# WL-Power.net
KiCad netlist of a schematic drawn in Altium Designer
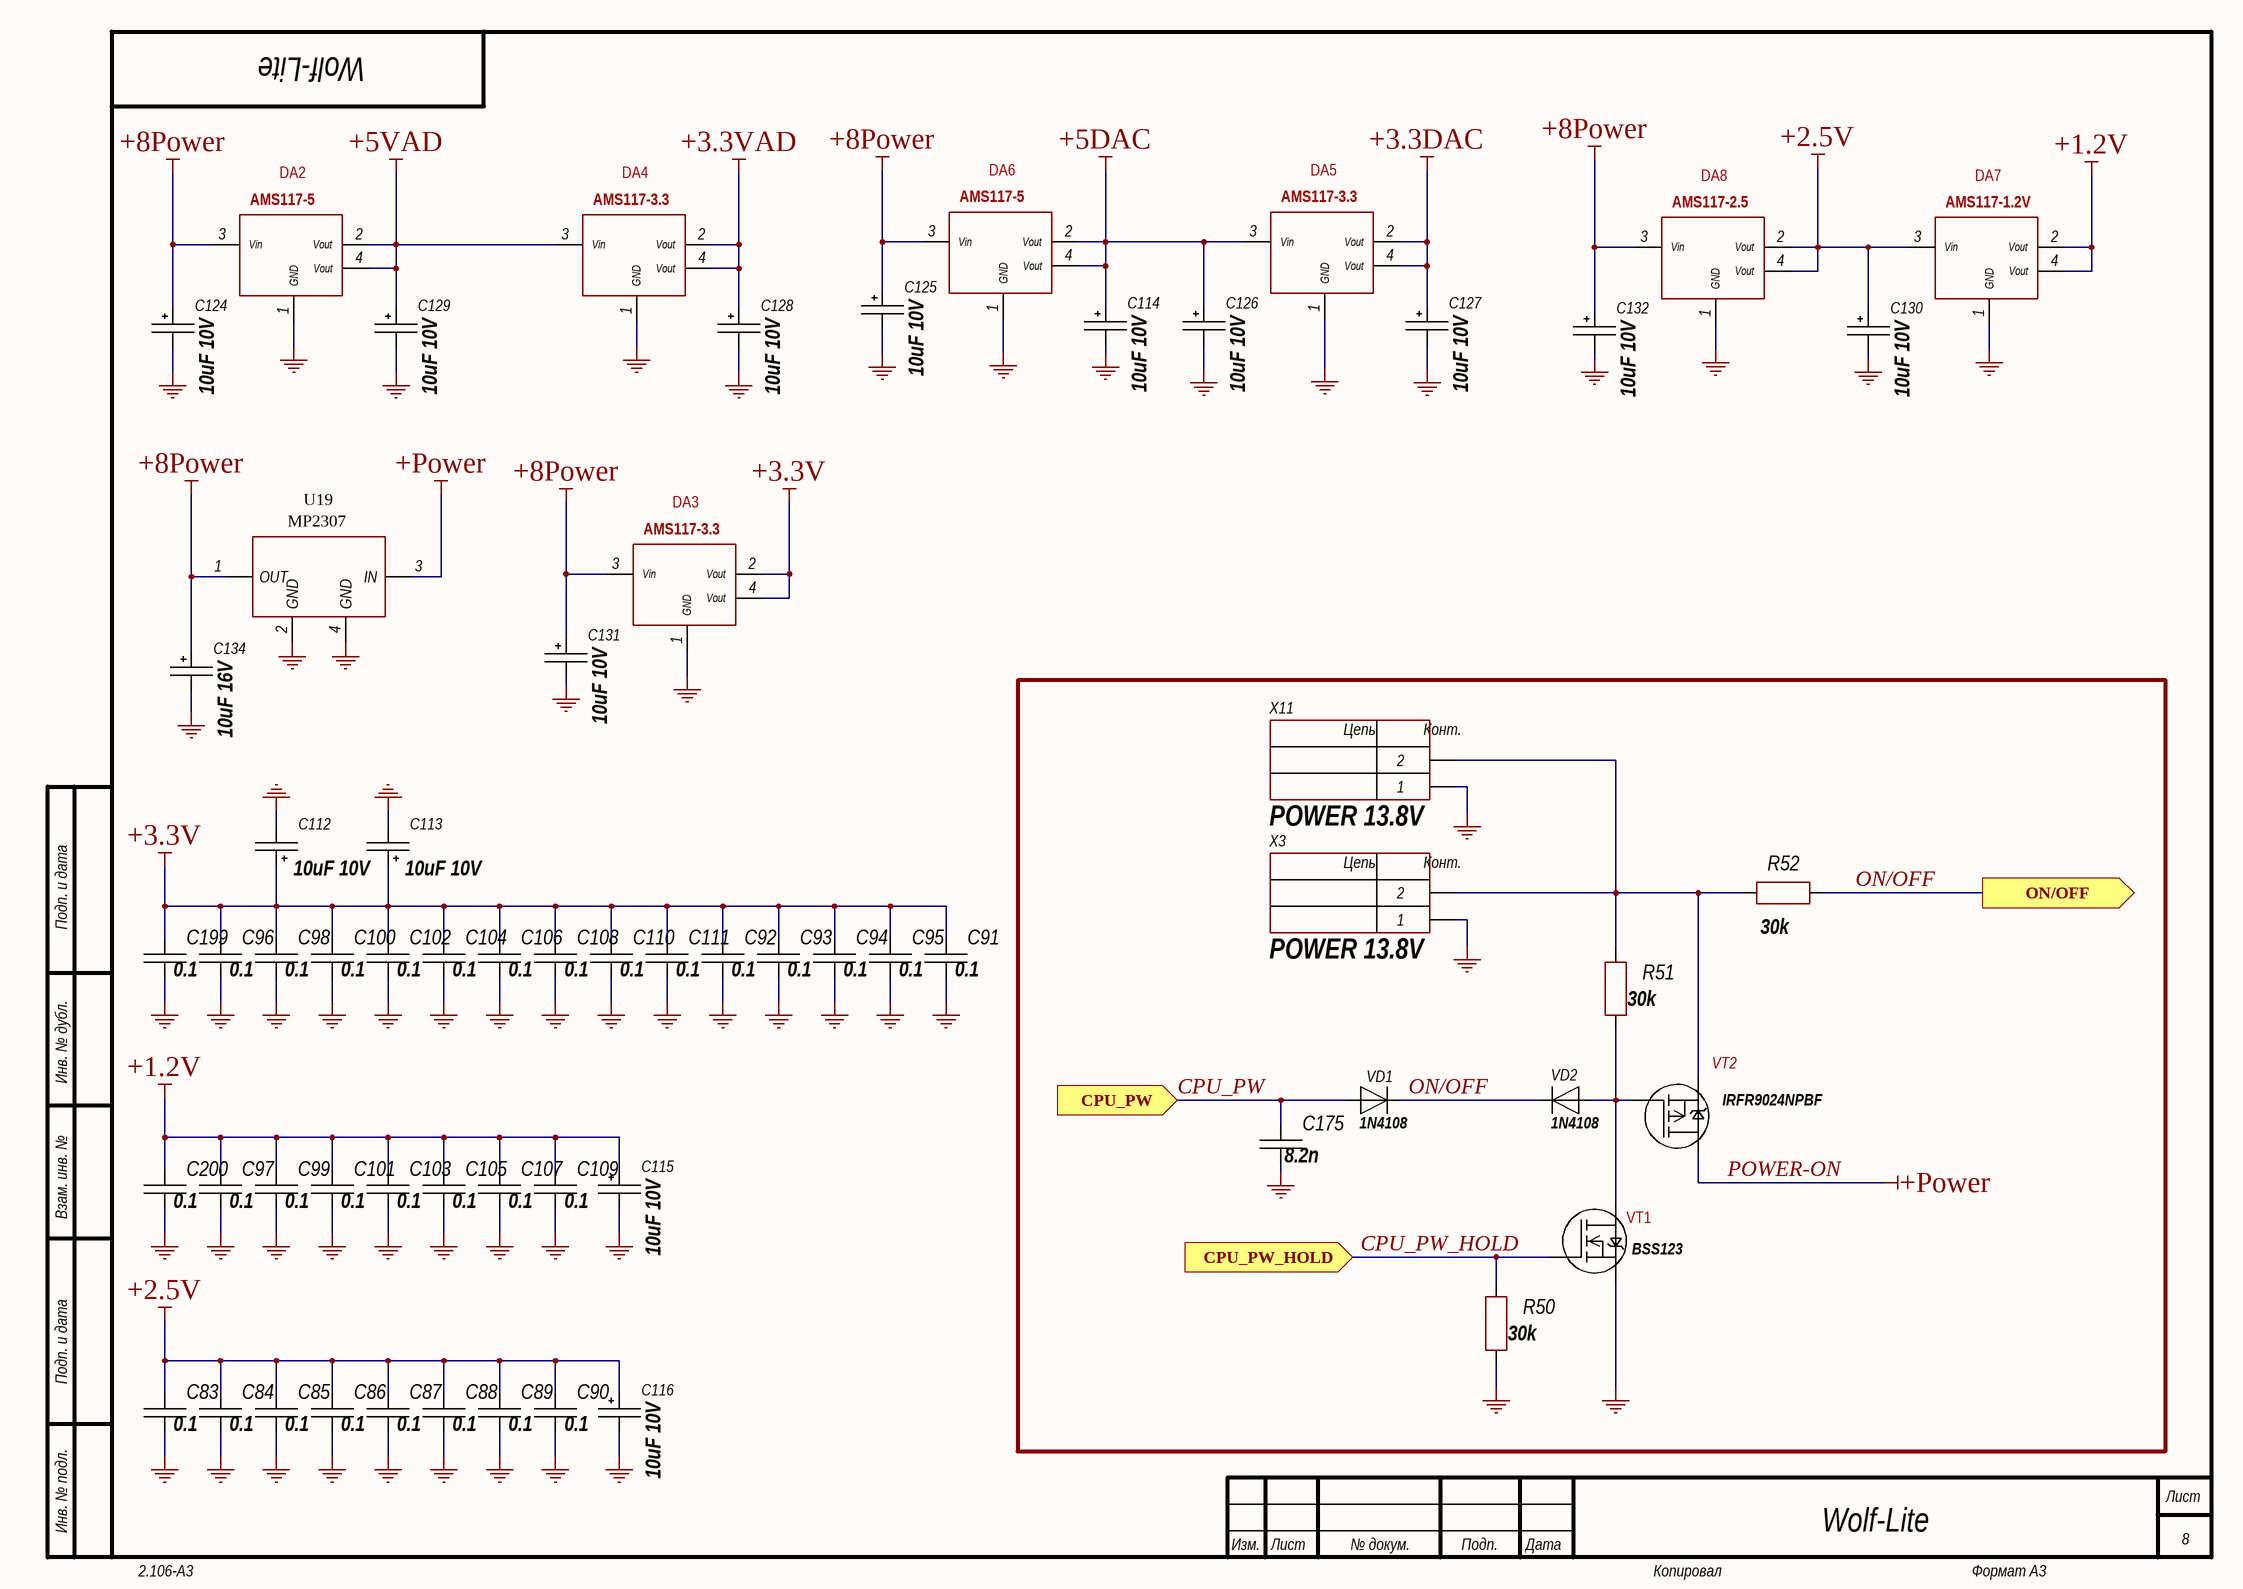
[diagram p0: WL-Power.SchDoc]

(export (version "E")
  (design (tool "Eeschema 10.0.6"))
  (components
    (comp (ref "C83")
      (value "0.1")
      (footprint "standard:CH0805C")
      (libsource (lib "Discrete") (part "Capacitor"))
    )
    (comp (ref "C84")
      (value "0.1")
      (footprint "standard:CH0805C")
      (libsource (lib "Discrete") (part "Capacitor"))
    )
    (comp (ref "C85")
      (value "0.1")
      (footprint "standard:CH0805C")
      (libsource (lib "Discrete") (part "Capacitor"))
    )
    (comp (ref "C86")
      (value "0.1")
      (footprint "standard:CH0805C")
      (libsource (lib "Discrete") (part "Capacitor"))
    )
    (comp (ref "C87")
      (value "0.1")
      (footprint "standard:CH0805C")
      (libsource (lib "Discrete") (part "Capacitor"))
    )
    (comp (ref "C88")
      (value "0.1")
      (footprint "standard:CH0805C")
      (libsource (lib "Discrete") (part "Capacitor"))
    )
    (comp (ref "C89")
      (value "0.1")
      (footprint "standard:CH0805C")
      (libsource (lib "Discrete") (part "Capacitor"))
    )
    (comp (ref "C90")
      (value "0.1")
      (footprint "standard:CH0805C")
      (libsource (lib "Discrete") (part "Capacitor"))
    )
    (comp (ref "C91")
      (value "0.1")
      (footprint "standard:CH0805C")
      (libsource (lib "Discrete") (part "Capacitor"))
    )
    (comp (ref "C92")
      (value "0.1")
      (footprint "standard:CH0805C")
      (libsource (lib "Discrete") (part "Capacitor"))
    )
    (comp (ref "C93")
      (value "0.1")
      (footprint "standard:CH0805C")
      (libsource (lib "Discrete") (part "Capacitor"))
    )
    (comp (ref "C94")
      (value "0.1")
      (footprint "standard:CH0805C")
      (libsource (lib "Discrete") (part "Capacitor"))
    )
    (comp (ref "C95")
      (value "0.1")
      (footprint "standard:CH0805C")
      (libsource (lib "Discrete") (part "Capacitor"))
    )
    (comp (ref "C96")
      (value "0.1")
      (footprint "standard:CH0805C")
      (libsource (lib "Discrete") (part "Capacitor"))
    )
    (comp (ref "C97")
      (value "0.1")
      (footprint "standard:CH0805C")
      (libsource (lib "Discrete") (part "Capacitor"))
    )
    (comp (ref "C98")
      (value "0.1")
      (footprint "standard:CH0805C")
      (libsource (lib "Discrete") (part "Capacitor"))
    )
    (comp (ref "C99")
      (value "0.1")
      (footprint "standard:CH0805C")
      (libsource (lib "Discrete") (part "Capacitor"))
    )
    (comp (ref "C100")
      (value "0.1")
      (footprint "standard:CH0805C")
      (libsource (lib "Discrete") (part "Capacitor"))
    )
    (comp (ref "C101")
      (value "0.1")
      (footprint "standard:CH0805C")
      (libsource (lib "Discrete") (part "Capacitor"))
    )
    (comp (ref "C102")
      (value "0.1")
      (footprint "standard:CH0805C")
      (libsource (lib "Discrete") (part "Capacitor"))
    )
    (comp (ref "C103")
      (value "0.1")
      (footprint "standard:CH0805C")
      (libsource (lib "Discrete") (part "Capacitor"))
    )
    (comp (ref "C104")
      (value "0.1")
      (footprint "standard:CH0805C")
      (libsource (lib "Discrete") (part "Capacitor"))
    )
    (comp (ref "C105")
      (value "0.1")
      (footprint "standard:CH0805C")
      (libsource (lib "Discrete") (part "Capacitor"))
    )
    (comp (ref "C106")
      (value "0.1")
      (footprint "standard:CH0805C")
      (libsource (lib "Discrete") (part "Capacitor"))
    )
    (comp (ref "C107")
      (value "0.1")
      (footprint "standard:CH0805C")
      (libsource (lib "Discrete") (part "Capacitor"))
    )
    (comp (ref "C108")
      (value "0.1")
      (footprint "standard:CH0805C")
      (libsource (lib "Discrete") (part "Capacitor"))
    )
    (comp (ref "C109")
      (value "0.1")
      (footprint "standard:CH0805C")
      (libsource (lib "Discrete") (part "Capacitor"))
    )
    (comp (ref "C110")
      (value "0.1")
      (footprint "standard:CH0805C")
      (libsource (lib "Discrete") (part "Capacitor"))
    )
    (comp (ref "C111")
      (value "0.1")
      (footprint "standard:CH0805C")
      (libsource (lib "Discrete") (part "Capacitor"))
    )
    (comp (ref "C112")
      (value "10uF 10V")
      (footprint "standard:TANTAL_B")
      (libsource (lib "Discrete") (part "TantalCap"))
    )
    (comp (ref "C113")
      (value "10uF 10V")
      (footprint "standard:TANTAL_B")
      (libsource (lib "Discrete") (part "TantalCap"))
    )
    (comp (ref "C114")
      (value "10uF 10V")
      (footprint "standard:TANTAL_B")
      (libsource (lib "Discrete") (part "TantalCap"))
    )
    (comp (ref "C115")
      (value "10uF 10V")
      (footprint "standard:TANTAL_B")
      (libsource (lib "Discrete") (part "TantalCap"))
    )
    (comp (ref "C116")
      (value "10uF 10V")
      (footprint "standard:TANTAL_B")
      (libsource (lib "Discrete") (part "TantalCap"))
    )
    (comp (ref "C124")
      (value "10uF 10V")
      (footprint "standard:TANTAL_B")
      (libsource (lib "Discrete") (part "TantalCap"))
    )
    (comp (ref "C125")
      (value "10uF 10V")
      (footprint "standard:TANTAL_B")
      (libsource (lib "Discrete") (part "TantalCap"))
    )
    (comp (ref "C126")
      (value "10uF 10V")
      (footprint "standard:TANTAL_B")
      (libsource (lib "Discrete") (part "TantalCap"))
    )
    (comp (ref "C127")
      (value "10uF 10V")
      (footprint "standard:TANTAL_B")
      (libsource (lib "Discrete") (part "TantalCap"))
    )
    (comp (ref "C128")
      (value "10uF 10V")
      (footprint "standard:TANTAL_B")
      (libsource (lib "Discrete") (part "TantalCap"))
    )
    (comp (ref "C129")
      (value "10uF 10V")
      (footprint "standard:TANTAL_B")
      (libsource (lib "Discrete") (part "TantalCap"))
    )
    (comp (ref "C130")
      (value "10uF 10V")
      (footprint "standard:TANTAL_B")
      (libsource (lib "Discrete") (part "TantalCap"))
    )
    (comp (ref "C131")
      (value "10uF 10V")
      (footprint "standard:TANTAL_B")
      (libsource (lib "Discrete") (part "TantalCap"))
    )
    (comp (ref "C132")
      (value "10uF 10V")
      (footprint "standard:TANTAL_B")
      (libsource (lib "Discrete") (part "TantalCap"))
    )
    (comp (ref "C134")
      (value "10uF 16V")
      (footprint "POLIMER-D")
      (libsource (lib "Discrete") (part "TantalCap"))
    )
    (comp (ref "C175")
      (value "8.2n")
      (footprint "standard:CH0805C")
      (libsource (lib "Discrete") (part "Capacitor"))
    )
    (comp (ref "C199")
      (value "0.1")
      (footprint "standard:CH0805C")
      (libsource (lib "Discrete") (part "Capacitor"))
    )
    (comp (ref "C200")
      (value "0.1")
      (footprint "standard:CH0805C")
      (libsource (lib "Discrete") (part "Capacitor"))
    )
    (comp (ref "DA2") (value "AMS117-5") (footprint "SOT223") (libsource (lib "Analog") (part "AMS117")))
    (comp (ref "DA3") (value "AMS117-3.3") (footprint "SOT223") (libsource (lib "Analog") (part "AMS117")))
    (comp (ref "DA4") (value "AMS117-3.3") (footprint "SOT223") (libsource (lib "Analog") (part "AMS117")))
    (comp (ref "DA5") (value "AMS117-3.3") (footprint "SOT223") (libsource (lib "Analog") (part "AMS117")))
    (comp (ref "DA6") (value "AMS117-5") (footprint "SOT223") (libsource (lib "Analog") (part "AMS117")))
    (comp (ref "DA7") (value "AMS117-1.2V") (footprint "SOT223") (libsource (lib "Analog") (part "AMS117")))
    (comp (ref "DA8") (value "AMS117-2.5") (footprint "SOT223") (libsource (lib "Analog") (part "AMS117")))
    (comp (ref "R50") (value "30k") (footprint "standard:CH0805R") (libsource (lib "") (part "Resistor_1")))
    (comp (ref "R51") (value "30k") (footprint "standard:CH0805R") (libsource (lib "") (part "Resistor_1")))
    (comp (ref "R52")
      (value "30k")
      (footprint "standard:CH0805R")
      (libsource (lib "Discrete") (part "Resistor"))
    )
    (comp (ref "U19")
      (value "MP2307")
      (footprint "MP2307 MINI360")
      (libsource (lib "Power Supplies") (part "MP2307"))
    )
    (comp (ref "VD1") (value "1N4108") (footprint "1N4148") (libsource (lib "Diods") (part "Diod")))
    (comp (ref "VD2") (value "1N4108") (footprint "1N4148") (libsource (lib "Diods") (part "Diod")))
    (comp (ref "VT1")
      (value "BSS123")
      (footprint "SOT23_132")
      (libsource (lib "Transistor") (part "N-KANAL"))
    )
    (comp (ref "VT2")
      (value "IRFR9024NPBF")
      (footprint "D2PAK_132")
      (libsource (lib "Transistor") (part "P-KANAL"))
    )
    (comp (ref "X3")
      (value "POWER 13.8V")
      (footprint "custom:CON: 300-02P-5.0")
      (libsource (lib "Connectors") (part "2-Connector"))
    )
    (comp (ref "X11")
      (value "POWER 13.8V")
      (footprint "custom:CON: 300-02P-5.0")
      (libsource (lib "Connectors") (part "2-Connector"))
    )
  )
  (nets
    (net (code "1") (name "+1.2V") (class "Default")
      (node (ref "C101") (pin "1") (pinfunction "1_1") (pintype "power_in"))
      (node (ref "C103") (pin "1") (pinfunction "1_1") (pintype "power_in"))
      (node (ref "C105") (pin "1") (pinfunction "1_1") (pintype "power_in"))
      (node (ref "C107") (pin "1") (pinfunction "1_1") (pintype "power_in"))
      (node (ref "C109") (pin "1") (pinfunction "1_1") (pintype "power_in"))
      (node (ref "C115") (pin "1") (pinfunction "1_1") (pintype "power_in"))
      (node (ref "C200") (pin "1") (pinfunction "1_1") (pintype "power_in"))
      (node (ref "C97") (pin "1") (pinfunction "1_1") (pintype "power_in"))
      (node (ref "C99") (pin "1") (pinfunction "1_1") (pintype "power_in"))
      (node (ref "DA7") (pin "2") (pinfunction "Vout_2") (pintype "passive"))
      (node (ref "DA7") (pin "4") (pinfunction "Vout_4") (pintype "passive"))
    )
    (net (code "2") (name "+2.5V") (class "Default")
      (node (ref "C116") (pin "1") (pinfunction "1_1") (pintype "power_in"))
      (node (ref "C130") (pin "1") (pinfunction "1_1") (pintype "power_in"))
      (node (ref "C83") (pin "1") (pinfunction "1_1") (pintype "power_in"))
      (node (ref "C84") (pin "1") (pinfunction "1_1") (pintype "power_in"))
      (node (ref "C85") (pin "1") (pinfunction "1_1") (pintype "power_in"))
      (node (ref "C86") (pin "1") (pinfunction "1_1") (pintype "power_in"))
      (node (ref "C87") (pin "1") (pinfunction "1_1") (pintype "power_in"))
      (node (ref "C88") (pin "1") (pinfunction "1_1") (pintype "power_in"))
      (node (ref "C89") (pin "1") (pinfunction "1_1") (pintype "power_in"))
      (node (ref "C90") (pin "1") (pinfunction "1_1") (pintype "power_in"))
      (node (ref "DA7") (pin "3") (pinfunction "Vin_3") (pintype "passive"))
      (node (ref "DA8") (pin "2") (pinfunction "Vout_2") (pintype "passive"))
      (node (ref "DA8") (pin "4") (pinfunction "Vout_4") (pintype "passive"))
    )
    (net (code "3") (name "+3.3DAC") (class "Default")
      (node (ref "C127") (pin "1") (pinfunction "1_1") (pintype "power_in"))
      (node (ref "DA5") (pin "2") (pinfunction "Vout_2") (pintype "passive"))
      (node (ref "DA5") (pin "4") (pinfunction "Vout_4") (pintype "passive"))
    )
    (net (code "4") (name "+3.3V") (class "Default")
      (node (ref "C100") (pin "1") (pinfunction "1_1") (pintype "power_in"))
      (node (ref "C102") (pin "1") (pinfunction "1_1") (pintype "power_in"))
      (node (ref "C104") (pin "1") (pinfunction "1_1") (pintype "power_in"))
      (node (ref "C106") (pin "1") (pinfunction "1_1") (pintype "power_in"))
      (node (ref "C108") (pin "1") (pinfunction "1_1") (pintype "power_in"))
      (node (ref "C110") (pin "1") (pinfunction "1_1") (pintype "power_in"))
      (node (ref "C111") (pin "1") (pinfunction "1_1") (pintype "power_in"))
      (node (ref "C112") (pin "1") (pinfunction "1_1") (pintype "power_in"))
      (node (ref "C113") (pin "1") (pinfunction "1_1") (pintype "power_in"))
      (node (ref "C199") (pin "1") (pinfunction "1_1") (pintype "power_in"))
      (node (ref "C91") (pin "1") (pinfunction "1_1") (pintype "power_in"))
      (node (ref "C92") (pin "1") (pinfunction "1_1") (pintype "power_in"))
      (node (ref "C93") (pin "1") (pinfunction "1_1") (pintype "power_in"))
      (node (ref "C94") (pin "1") (pinfunction "1_1") (pintype "power_in"))
      (node (ref "C95") (pin "1") (pinfunction "1_1") (pintype "power_in"))
      (node (ref "C96") (pin "1") (pinfunction "1_1") (pintype "power_in"))
      (node (ref "C98") (pin "1") (pinfunction "1_1") (pintype "power_in"))
      (node (ref "DA3") (pin "2") (pinfunction "Vout_2") (pintype "passive"))
      (node (ref "DA3") (pin "4") (pinfunction "Vout_4") (pintype "passive"))
    )
    (net (code "5") (name "+3.3VAD") (class "Default")
      (node (ref "C128") (pin "1") (pinfunction "1_1") (pintype "power_in"))
      (node (ref "DA4") (pin "2") (pinfunction "Vout_2") (pintype "passive"))
      (node (ref "DA4") (pin "4") (pinfunction "Vout_4") (pintype "passive"))
    )
    (net (code "6") (name "+5DAC") (class "Default")
      (node (ref "C114") (pin "1") (pinfunction "1_1") (pintype "power_in"))
      (node (ref "C126") (pin "1") (pinfunction "1_1") (pintype "power_in"))
      (node (ref "DA5") (pin "3") (pinfunction "Vin_3") (pintype "passive"))
      (node (ref "DA6") (pin "2") (pinfunction "Vout_2") (pintype "passive"))
      (node (ref "DA6") (pin "4") (pinfunction "Vout_4") (pintype "passive"))
    )
    (net (code "7") (name "+5VAD") (class "Default")
      (node (ref "C129") (pin "1") (pinfunction "1_1") (pintype "power_in"))
      (node (ref "DA2") (pin "2") (pinfunction "Vout_2") (pintype "passive"))
      (node (ref "DA2") (pin "4") (pinfunction "Vout_4") (pintype "passive"))
      (node (ref "DA4") (pin "3") (pinfunction "Vin_3") (pintype "passive"))
    )
    (net (code "8") (name "+8Power") (class "Default")
      (node (ref "C124") (pin "1") (pinfunction "1_1") (pintype "power_in"))
      (node (ref "C125") (pin "1") (pinfunction "1_1") (pintype "power_in"))
      (node (ref "C131") (pin "1") (pinfunction "1_1") (pintype "power_in"))
      (node (ref "C132") (pin "1") (pinfunction "1_1") (pintype "power_in"))
      (node (ref "C134") (pin "1") (pinfunction "1_1") (pintype "power_in"))
      (node (ref "DA2") (pin "3") (pinfunction "Vin_3") (pintype "passive"))
      (node (ref "DA3") (pin "3") (pinfunction "Vin_3") (pintype "passive"))
      (node (ref "DA6") (pin "3") (pinfunction "Vin_3") (pintype "passive"))
      (node (ref "DA8") (pin "3") (pinfunction "Vin_3") (pintype "passive"))
      (node (ref "U19") (pin "1") (pinfunction "OUT_1") (pintype "power_in"))
    )
    (net (code "9") (name "+Power") (class "Default")
      (node (ref "U19") (pin "3") (pinfunction "IN_3") (pintype "passive"))
      (node (ref "VT2") (pin "3") (pinfunction "D_3") (pintype "passive"))
    )
    (net (code "10") (name "/CPU_PW") (class "Default")
      (node (ref "C175") (pin "1") (pinfunction "1_1") (pintype "power_in"))
      (node (ref "VD1") (pin "1") (pinfunction "1_1") (pintype "passive"))
    )
    (net (code "11") (name "/CPU_PW_HOLD") (class "Default")
      (node (ref "R50") (pin "2") (pinfunction "2_2") (pintype "passive"))
      (node (ref "VT1") (pin "1") (pinfunction "Затвор(Gate)_1") (pintype "passive"))
    )
    (net (code "12") (name "/ON{slash}OFF") (class "Default")
      (node (ref "R52") (pin "1") (pinfunction "1_1") (pintype "passive"))
      (node (ref "VD1") (pin "2") (pinfunction "2_2") (pintype "passive"))
      (node (ref "VD2") (pin "2") (pinfunction "2_2") (pintype "passive"))
    )
    (net (code "13") (name "GND") (class "Default")
      (node (ref "C100") (pin "2") (pinfunction "2_2") (pintype "power_in"))
      (node (ref "C101") (pin "2") (pinfunction "2_2") (pintype "power_in"))
      (node (ref "C102") (pin "2") (pinfunction "2_2") (pintype "power_in"))
      (node (ref "C103") (pin "2") (pinfunction "2_2") (pintype "power_in"))
      (node (ref "C104") (pin "2") (pinfunction "2_2") (pintype "power_in"))
      (node (ref "C105") (pin "2") (pinfunction "2_2") (pintype "power_in"))
      (node (ref "C106") (pin "2") (pinfunction "2_2") (pintype "power_in"))
      (node (ref "C107") (pin "2") (pinfunction "2_2") (pintype "power_in"))
      (node (ref "C108") (pin "2") (pinfunction "2_2") (pintype "power_in"))
      (node (ref "C109") (pin "2") (pinfunction "2_2") (pintype "power_in"))
      (node (ref "C110") (pin "2") (pinfunction "2_2") (pintype "power_in"))
      (node (ref "C111") (pin "2") (pinfunction "2_2") (pintype "power_in"))
      (node (ref "C112") (pin "2") (pinfunction "2_2") (pintype "power_in"))
      (node (ref "C113") (pin "2") (pinfunction "2_2") (pintype "power_in"))
      (node (ref "C114") (pin "2") (pinfunction "2_2") (pintype "power_in"))
      (node (ref "C115") (pin "2") (pinfunction "2_2") (pintype "power_in"))
      (node (ref "C116") (pin "2") (pinfunction "2_2") (pintype "power_in"))
      (node (ref "C124") (pin "2") (pinfunction "2_2") (pintype "power_in"))
      (node (ref "C125") (pin "2") (pinfunction "2_2") (pintype "power_in"))
      (node (ref "C126") (pin "2") (pinfunction "2_2") (pintype "power_in"))
      (node (ref "C127") (pin "2") (pinfunction "2_2") (pintype "power_in"))
      (node (ref "C128") (pin "2") (pinfunction "2_2") (pintype "power_in"))
      (node (ref "C129") (pin "2") (pinfunction "2_2") (pintype "power_in"))
      (node (ref "C130") (pin "2") (pinfunction "2_2") (pintype "power_in"))
      (node (ref "C131") (pin "2") (pinfunction "2_2") (pintype "power_in"))
      (node (ref "C132") (pin "2") (pinfunction "2_2") (pintype "power_in"))
      (node (ref "C134") (pin "2") (pinfunction "2_2") (pintype "power_in"))
      (node (ref "C175") (pin "2") (pinfunction "2_2") (pintype "power_in"))
      (node (ref "C199") (pin "2") (pinfunction "2_2") (pintype "power_in"))
      (node (ref "C200") (pin "2") (pinfunction "2_2") (pintype "power_in"))
      (node (ref "C83") (pin "2") (pinfunction "2_2") (pintype "power_in"))
      (node (ref "C84") (pin "2") (pinfunction "2_2") (pintype "power_in"))
      (node (ref "C85") (pin "2") (pinfunction "2_2") (pintype "power_in"))
      (node (ref "C86") (pin "2") (pinfunction "2_2") (pintype "power_in"))
      (node (ref "C87") (pin "2") (pinfunction "2_2") (pintype "power_in"))
      (node (ref "C88") (pin "2") (pinfunction "2_2") (pintype "power_in"))
      (node (ref "C89") (pin "2") (pinfunction "2_2") (pintype "power_in"))
      (node (ref "C90") (pin "2") (pinfunction "2_2") (pintype "power_in"))
      (node (ref "C91") (pin "2") (pinfunction "2_2") (pintype "power_in"))
      (node (ref "C92") (pin "2") (pinfunction "2_2") (pintype "power_in"))
      (node (ref "C93") (pin "2") (pinfunction "2_2") (pintype "power_in"))
      (node (ref "C94") (pin "2") (pinfunction "2_2") (pintype "power_in"))
      (node (ref "C95") (pin "2") (pinfunction "2_2") (pintype "power_in"))
      (node (ref "C96") (pin "2") (pinfunction "2_2") (pintype "power_in"))
      (node (ref "C97") (pin "2") (pinfunction "2_2") (pintype "power_in"))
      (node (ref "C98") (pin "2") (pinfunction "2_2") (pintype "power_in"))
      (node (ref "C99") (pin "2") (pinfunction "2_2") (pintype "power_in"))
      (node (ref "DA2") (pin "1") (pinfunction "GND_1") (pintype "passive"))
      (node (ref "DA3") (pin "1") (pinfunction "GND_1") (pintype "passive"))
      (node (ref "DA4") (pin "1") (pinfunction "GND_1") (pintype "passive"))
      (node (ref "DA5") (pin "1") (pinfunction "GND_1") (pintype "passive"))
      (node (ref "DA6") (pin "1") (pinfunction "GND_1") (pintype "passive"))
      (node (ref "DA7") (pin "1") (pinfunction "GND_1") (pintype "passive"))
      (node (ref "DA8") (pin "1") (pinfunction "GND_1") (pintype "passive"))
      (node (ref "R50") (pin "1") (pinfunction "1_1") (pintype "passive"))
      (node (ref "U19") (pin "2") (pinfunction "GND_2") (pintype "passive"))
      (node (ref "U19") (pin "4") (pinfunction "GND_4") (pintype "passive"))
      (node (ref "VT1") (pin "2") (pinfunction "I_2") (pintype "passive"))
      (node (ref "X11") (pin "1") (pinfunction "1_1") (pintype "passive"))
      (node (ref "X3") (pin "1") (pinfunction "1_1") (pintype "passive"))
    )
    (net (code "14") (name "Net-(VT1-Сток(Drain))") (class "Default")
      (node (ref "R51") (pin "1") (pinfunction "1_1") (pintype "passive"))
      (node (ref "VD2") (pin "1") (pinfunction "1_1") (pintype "passive"))
      (node (ref "VT1") (pin "3") (pinfunction "Сток(Drain)_3") (pintype "passive"))
      (node (ref "VT2") (pin "1") (pinfunction "Затвор(Gate)_1") (pintype "passive"))
    )
    (net (code "15") (name "Net-(VT2-S)") (class "Default")
      (node (ref "R51") (pin "2") (pinfunction "2_2") (pintype "passive"))
      (node (ref "R52") (pin "2") (pinfunction "2_2") (pintype "passive"))
      (node (ref "VT2") (pin "2") (pinfunction "S_2") (pintype "passive"))
      (node (ref "X11") (pin "2") (pinfunction "2_2") (pintype "passive"))
      (node (ref "X3") (pin "2") (pinfunction "2_2") (pintype "passive"))
    )
  )
)
